# Qduino_Mini.net
KiCad netlist of a schematic drawn in EAGLE
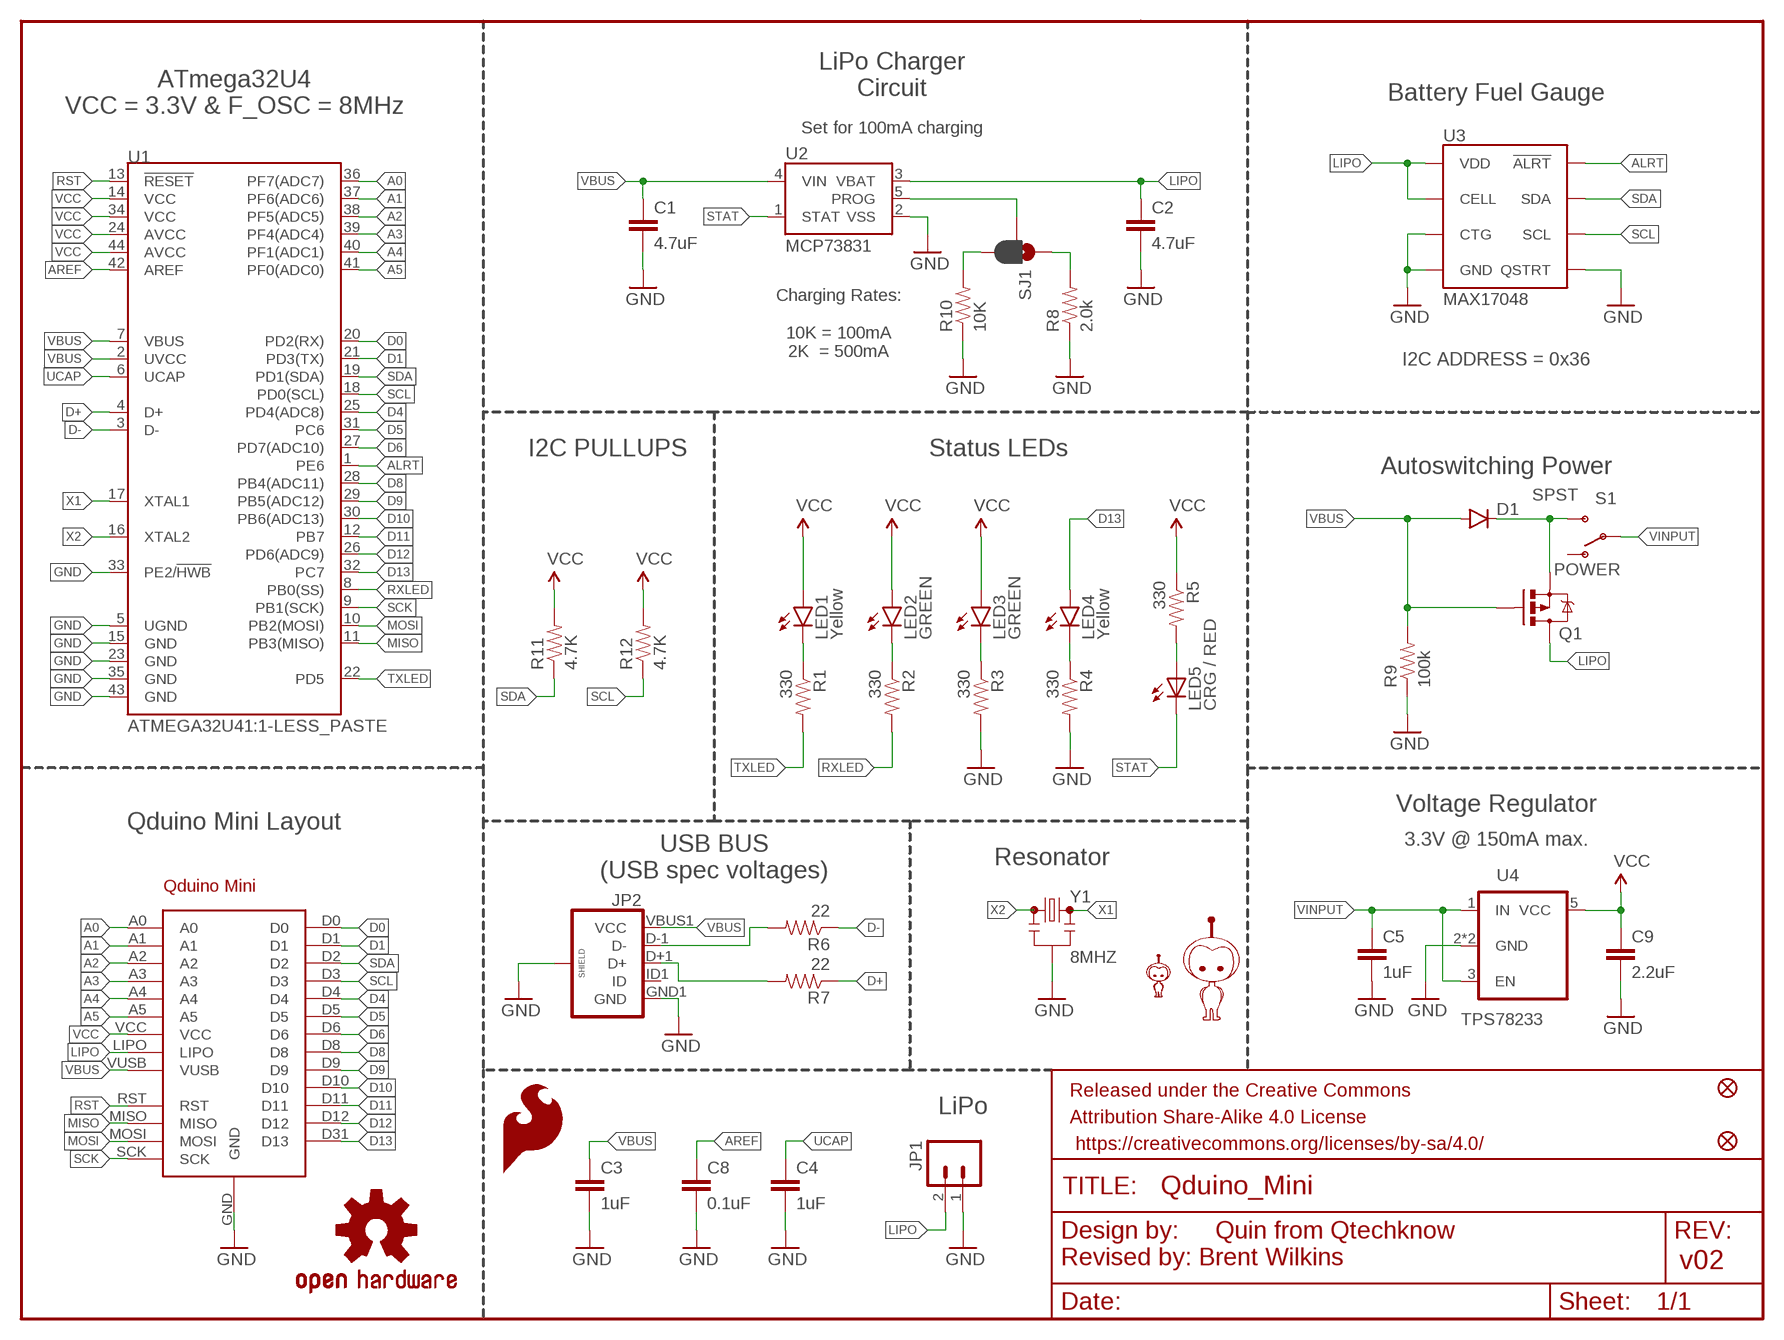
[diagram p0: schematic, sheet 1]

(export (version "E")
  (design (tool "Eeschema 10.0.6"))
  (components
    (comp (ref "C1")
      (value "4.7uF")
      (footprint "eagle-import:0603-CAP")
      (libsource (lib "eagle-import") (part "CAP0603-CAP"))
    )
    (comp (ref "C2")
      (value "4.7uF")
      (footprint "eagle-import:0603-CAP")
      (libsource (lib "eagle-import") (part "CAP0603-CAP"))
    )
    (comp (ref "C3")
      (value "1uF")
      (footprint "eagle-import:0603-CAP")
      (libsource (lib "eagle-import") (part "CAP0603-CAP"))
    )
    (comp (ref "C4")
      (value "1uF")
      (footprint "eagle-import:0603-CAP")
      (libsource (lib "eagle-import") (part "CAP0603-CAP"))
    )
    (comp (ref "C5")
      (value "1uF")
      (footprint "eagle-import:0603-CAP")
      (libsource (lib "eagle-import") (part "CAP0603-CAP"))
    )
    (comp (ref "C8")
      (value "0.1uF")
      (footprint "eagle-import:0603-CAP")
      (libsource (lib "eagle-import") (part "0.1UF-25V(+80/-20%)(0603)"))
    )
    (comp (ref "C9")
      (value "2.2uF")
      (footprint "eagle-import:0603-CAP")
      (libsource (lib "eagle-import") (part "2.2UF-10V-20%(0603)"))
    )
    (comp (ref "D1")
      (value "250mA/100V")
      (footprint "eagle-import:SOD-323")
      (libsource (lib "eagle-import") (part "DIODEBAS16"))
    )
    (comp (ref "FID5")
      (value "FIDUCIAL1X2")
      (footprint "eagle-import:FIDUCIAL-1X2")
      (libsource (lib "eagle-import") (part "FIDUCIAL1X2"))
    )
    (comp (ref "FID6")
      (value "FIDUCIAL1X2")
      (footprint "eagle-import:FIDUCIAL-1X2")
      (libsource (lib "eagle-import") (part "FIDUCIAL1X2"))
    )
    (comp (ref "FRAME2")
      (value "FRAME-LETTER")
      (footprint "eagle-import:CREATIVE_COMMONS")
      (fields (field (name "DESIGNER") "NAME"))
      (libsource (lib "eagle-import") (part "FRAME-LETTER"))
    )
    (comp (ref "JP1")
      (value "LiPo")
      (footprint "eagle-import:JST-2-SMD")
      (libsource (lib "eagle-import") (part "M02-JST-2MM-SMT"))
    )
    (comp (ref "JP2")
      (value "USB_MICROB_PLUGCONN-11752")
      (footprint "eagle-import:USB-B-MICRO-SMD_V03")
      (libsource (lib "eagle-import") (part "USB_MICROB_PLUGCONN-11752"))
    )
    (comp (ref "LED1")
      (value "Yellow")
      (footprint "eagle-import:LED-0603")
      (fields (field (name "PROD_ID") "DIO-09003"))
      (libsource (lib "eagle-import") (part "LED-YELLOW0603"))
    )
    (comp (ref "LED2")
      (value "GREEN")
      (footprint "eagle-import:LED-0603")
      (fields (field (name "PROD_ID") "DIO-00821"))
      (libsource (lib "eagle-import") (part "LED-GREEN0603"))
    )
    (comp (ref "LED3")
      (value "GREEN")
      (footprint "eagle-import:LED-0603")
      (fields (field (name "PROD_ID") "DIO-00821"))
      (libsource (lib "eagle-import") (part "LED-GREEN0603"))
    )
    (comp (ref "LED4")
      (value "Yellow")
      (footprint "eagle-import:LED-0603")
      (fields (field (name "PROD_ID") "DIO-09003"))
      (libsource (lib "eagle-import") (part "LED-YELLOW0603"))
    )
    (comp (ref "LED5")
      (value "CRG / RED")
      (footprint "eagle-import:LED-0603")
      (libsource (lib "eagle-import") (part "LED0603"))
    )
    (comp (ref "LOGO1")
      (value "OSHW-LOGOS")
      (footprint "eagle-import:OSHW-LOGO-S")
      (libsource (lib "eagle-import") (part "OSHW-LOGOS"))
    )
    (comp (ref "LOGO2")
      (value "SFE_LOGO_FLAME.1_INCH")
      (footprint "eagle-import:SFE_LOGO_FLAME_.1")
      (libsource (lib "eagle-import") (part "SFE_LOGO_FLAME.1_INCH"))
    )
    (comp (ref "Q1")
      (value "PFET")
      (footprint "eagle-import:SOT23-3")
      (libsource (lib "eagle-import") (part "MOSFET-PCHANNEL"))
    )
    (comp (ref "R1")
      (value "330")
      (footprint "eagle-import:0603-RES")
      (libsource (lib "eagle-import") (part "RESISTOR0603"))
    )
    (comp (ref "R2")
      (value "330")
      (footprint "eagle-import:0603-RES")
      (libsource (lib "eagle-import") (part "RESISTOR0603"))
    )
    (comp (ref "R3")
      (value "330")
      (footprint "eagle-import:0603-RES")
      (libsource (lib "eagle-import") (part "RESISTOR0603"))
    )
    (comp (ref "R4")
      (value "330")
      (footprint "eagle-import:0603-RES")
      (libsource (lib "eagle-import") (part "RESISTOR0603"))
    )
    (comp (ref "R5")
      (value "330")
      (footprint "eagle-import:0603-RES")
      (libsource (lib "eagle-import") (part "RESISTOR0603"))
    )
    (comp (ref "R6")
      (value "22")
      (footprint "eagle-import:0603-RES")
      (libsource (lib "eagle-import") (part "RESISTOR0603"))
    )
    (comp (ref "R7")
      (value "22")
      (footprint "eagle-import:0603-RES")
      (libsource (lib "eagle-import") (part "RESISTOR0603"))
    )
    (comp (ref "R8")
      (value "2.0k")
      (footprint "eagle-import:0603-RES")
      (libsource (lib "eagle-import") (part "2.0KOHM1/10W5%(0603)"))
    )
    (comp (ref "R9")
      (value "100k")
      (footprint "eagle-import:0603-RES")
      (libsource (lib "eagle-import") (part "100KOHM-1/10W-1%(0603)"))
    )
    (comp (ref "R10")
      (value "10K")
      (footprint "eagle-import:0603-RES")
      (libsource (lib "eagle-import") (part "10KOHM-1/10W-1%(0603)0603"))
    )
    (comp (ref "R11")
      (value "4.7K")
      (footprint "eagle-import:0603-RES")
      (libsource (lib "eagle-import") (part "RESISTOR0603-RES"))
    )
    (comp (ref "R12")
      (value "4.7K")
      (footprint "eagle-import:0603-RES")
      (libsource (lib "eagle-import") (part "RESISTOR0603-RES"))
    )
    (comp (ref "S1")
      (value "POWER")
      (footprint "eagle-import:SWITCH-SPST-SMD-A")
      (libsource (lib "eagle-import") (part "SWITCH-SPDT-SMD-A"))
    )
    (comp (ref "SJ1")
      (value "JUMPER-PAD-3-2OF3_NC_BY_PASTE")
      (footprint "eagle-import:PAD-JUMPER-3-2OF3_NC_BY_PASTE_YES_SILK_FULL_BOX")
      (libsource (lib "eagle-import") (part "JUMPER-PAD-3-2OF3_NC_BY_PASTE"))
    )
    (comp (ref "U1")
      (value "ATMEGA32U41:1-LESS_PASTE")
      (footprint "eagle-import:QFN-44-NOPAD_1_1-LESS_PASTE")
      (libsource (lib "eagle-import") (part "ATMEGA32U41{colon}1-LESS_PASTE"))
    )
    (comp (ref "U2")
      (value "MCP73831")
      (footprint "eagle-import:SOT23-5")
      (libsource (lib "eagle-import") (part "MCP73831"))
    )
    (comp (ref "U3")
      (value "MAX17048")
      (footprint "eagle-import:DFN-8")
      (libsource (lib "eagle-import") (part "MAX17048DFN8"))
    )
    (comp (ref "U4")
      (value "TPS78233")
      (footprint "eagle-import:SOT23-5")
      (libsource (lib "eagle-import") (part "LDO-TPS78233"))
    )
    (comp (ref "U5")
      (value "MIGHTYQ-L-SILK")
      (footprint "eagle-import:LOGO-LARGE-SILK")
      (libsource (lib "eagle-import") (part "MIGHTYQ-L-SILK"))
    )
    (comp (ref "U6")
      (value "MIGHTYQ-S-SILK")
      (footprint "eagle-import:LOGO-SMALL-SILK")
      (libsource (lib "eagle-import") (part "MIGHTYQ-S-SILK"))
    )
    (comp (ref "U7")
      (value "DNP")
      (footprint "eagle-import:QDUINO_MINI_V15")
      (libsource (lib "eagle-import") (part "QDUINOMINI"))
    )
    (comp (ref "Y1")
      (value "8MHZ")
      (footprint "eagle-import:RESONATOR-SMD")
      (libsource (lib "eagle-import") (part "RESONATOR8MHZ"))
    )
  )
  (nets
    (net (code "1") (name "A0") (class "Default")
      (node (ref "U1") (pin "36") (pinfunction "PF7(ADC7)_36") (pintype "bidirectional"))
      (node (ref "U7") (pin "A0") (pinfunction "A0_A0") (pintype "bidirectional"))
    )
    (net (code "2") (name "A1") (class "Default")
      (node (ref "U1") (pin "37") (pinfunction "PF6(ADC6)_37") (pintype "bidirectional"))
      (node (ref "U7") (pin "A1") (pinfunction "A1_A1") (pintype "bidirectional"))
    )
    (net (code "3") (name "A2") (class "Default")
      (node (ref "U1") (pin "38") (pinfunction "PF5(ADC5)_38") (pintype "bidirectional"))
      (node (ref "U7") (pin "A2") (pinfunction "A2_A2") (pintype "bidirectional"))
    )
    (net (code "4") (name "A3") (class "Default")
      (node (ref "U1") (pin "39") (pinfunction "PF4(ADC4)_39") (pintype "bidirectional"))
      (node (ref "U7") (pin "A3") (pinfunction "A3_A3") (pintype "bidirectional"))
    )
    (net (code "5") (name "A4") (class "Default")
      (node (ref "U1") (pin "40") (pinfunction "PF1(ADC1)_40") (pintype "bidirectional"))
      (node (ref "U7") (pin "A4") (pinfunction "A4_A4") (pintype "bidirectional"))
    )
    (net (code "6") (name "A5") (class "Default")
      (node (ref "U1") (pin "41") (pinfunction "PF0(ADC0)_41") (pintype "bidirectional"))
      (node (ref "U7") (pin "A5") (pinfunction "A5_A5") (pintype "bidirectional"))
    )
    (net (code "7") (name "ALRT") (class "Default")
      (node (ref "U1") (pin "1") (pinfunction "PE6_1") (pintype "bidirectional"))
      (node (ref "U3") (pin "P$5") (pinfunction "~{ALRT}_P$5") (pintype "bidirectional"))
    )
    (net (code "8") (name "AREF") (class "Default")
      (node (ref "C8") (pin "1") (pinfunction "1_1") (pintype "passive"))
      (node (ref "U1") (pin "42") (pinfunction "AREF_42") (pintype "bidirectional"))
    )
    (net (code "9") (name "D+") (class "Default")
      (node (ref "R7") (pin "1") (pinfunction "1_1") (pintype "passive"))
      (node (ref "U1") (pin "4") (pinfunction "D+_4") (pintype "bidirectional"))
    )
    (net (code "10") (name "D-") (class "Default")
      (node (ref "R6") (pin "1") (pinfunction "1_1") (pintype "passive"))
      (node (ref "U1") (pin "3") (pinfunction "D-_3") (pintype "bidirectional"))
    )
    (net (code "11") (name "D0") (class "Default")
      (node (ref "U1") (pin "20") (pinfunction "PD2(RX)_20") (pintype "bidirectional"))
      (node (ref "U7") (pin "D0") (pinfunction "D0_D0") (pintype "bidirectional"))
    )
    (net (code "12") (name "D1") (class "Default")
      (node (ref "U1") (pin "21") (pinfunction "PD3(TX)_21") (pintype "bidirectional"))
      (node (ref "U7") (pin "D1") (pinfunction "D1_D1") (pintype "bidirectional"))
    )
    (net (code "13") (name "D4") (class "Default")
      (node (ref "U1") (pin "25") (pinfunction "PD4(ADC8)_25") (pintype "bidirectional"))
      (node (ref "U7") (pin "D4") (pinfunction "D4_D4") (pintype "bidirectional"))
    )
    (net (code "14") (name "D5") (class "Default")
      (node (ref "U1") (pin "31") (pinfunction "PC6_31") (pintype "bidirectional"))
      (node (ref "U7") (pin "D5") (pinfunction "D5_D5") (pintype "bidirectional"))
    )
    (net (code "15") (name "D6") (class "Default")
      (node (ref "U1") (pin "27") (pinfunction "PD7(ADC10)_27") (pintype "bidirectional"))
      (node (ref "U7") (pin "D6") (pinfunction "D6_D6") (pintype "bidirectional"))
    )
    (net (code "16") (name "D8") (class "Default")
      (node (ref "U1") (pin "28") (pinfunction "PB4(ADC11)_28") (pintype "bidirectional"))
      (node (ref "U7") (pin "D8") (pinfunction "D8_D8") (pintype "bidirectional"))
    )
    (net (code "17") (name "D9") (class "Default")
      (node (ref "U1") (pin "29") (pinfunction "PB5(ADC12)_29") (pintype "bidirectional"))
      (node (ref "U7") (pin "D9") (pinfunction "D9_D9") (pintype "bidirectional"))
    )
    (net (code "18") (name "D10") (class "Default")
      (node (ref "U1") (pin "30") (pinfunction "PB6(ADC13)_30") (pintype "bidirectional"))
      (node (ref "U7") (pin "D10") (pinfunction "D10_D10") (pintype "bidirectional"))
    )
    (net (code "19") (name "D11") (class "Default")
      (node (ref "U1") (pin "12") (pinfunction "PB7_12") (pintype "bidirectional"))
      (node (ref "U7") (pin "D11") (pinfunction "D11_D11") (pintype "bidirectional"))
    )
    (net (code "20") (name "D12") (class "Default")
      (node (ref "U1") (pin "26") (pinfunction "PD6(ADC9)_26") (pintype "bidirectional"))
      (node (ref "U7") (pin "D12") (pinfunction "D12_D12") (pintype "bidirectional"))
    )
    (net (code "21") (name "D13") (class "Default")
      (node (ref "LED4") (pin "A") (pinfunction "A_A") (pintype "passive"))
      (node (ref "U1") (pin "32") (pinfunction "PC7_32") (pintype "bidirectional"))
      (node (ref "U7") (pin "D31") (pinfunction "D13_D31") (pintype "bidirectional"))
    )
    (net (code "22") (name "GND") (class "Default")
      (node (ref "C1") (pin "2") (pinfunction "2_2") (pintype "passive"))
      (node (ref "C2") (pin "2") (pinfunction "2_2") (pintype "passive"))
      (node (ref "C3") (pin "2") (pinfunction "2_2") (pintype "passive"))
      (node (ref "C4") (pin "2") (pinfunction "2_2") (pintype "passive"))
      (node (ref "C5") (pin "2") (pinfunction "2_2") (pintype "passive"))
      (node (ref "C8") (pin "2") (pinfunction "2_2") (pintype "passive"))
      (node (ref "C9") (pin "2") (pinfunction "2_2") (pintype "passive"))
      (node (ref "JP1") (pin "1") (pinfunction "1_1") (pintype "passive"))
      (node (ref "JP2") (pin "GND1") (pinfunction "GND_GND1") (pintype "bidirectional"))
      (node (ref "JP2") (pin "SHIELD1") (pinfunction "SHIELD_SHIELD1") (pintype "bidirectional"))
      (node (ref "JP2") (pin "SHIELD2") (pinfunction "SHIELD_SHIELD2") (pintype "bidirectional"))
      (node (ref "JP2") (pin "SHIELD3") (pinfunction "SHIELD_SHIELD3") (pintype "bidirectional"))
      (node (ref "R10") (pin "1") (pinfunction "1_1") (pintype "passive"))
      (node (ref "R3") (pin "2") (pinfunction "2_2") (pintype "passive"))
      (node (ref "R4") (pin "2") (pinfunction "2_2") (pintype "passive"))
      (node (ref "R8") (pin "1") (pinfunction "1_1") (pintype "passive"))
      (node (ref "R9") (pin "1") (pinfunction "1_1") (pintype "passive"))
      (node (ref "U1") (pin "15") (pinfunction "GND_15") (pintype "bidirectional"))
      (node (ref "U1") (pin "23") (pinfunction "GND_23") (pintype "bidirectional"))
      (node (ref "U1") (pin "33") (pinfunction "PE2/~{HWB}_33") (pintype "bidirectional"))
      (node (ref "U1") (pin "35") (pinfunction "GND_35") (pintype "bidirectional"))
      (node (ref "U1") (pin "43") (pinfunction "GND_43") (pintype "bidirectional"))
      (node (ref "U1") (pin "5") (pinfunction "UGND_5") (pintype "bidirectional"))
      (node (ref "U2") (pin "2") (pinfunction "VSS_2") (pintype "power_in"))
      (node (ref "U3") (pin "P$1") (pinfunction "CTG_P$1") (pintype "input"))
      (node (ref "U3") (pin "P$4") (pinfunction "GND_P$4") (pintype "bidirectional"))
      (node (ref "U3") (pin "P$6") (pinfunction "QSTRT_P$6") (pintype "bidirectional"))
      (node (ref "U3") (pin "P$9") (pinfunction "GND_P$9") (pintype "bidirectional"))
      (node (ref "U4") (pin "2") (pinfunction "GND_2") (pintype "input"))
      (node (ref "U4") (pin "4") (pinfunction "GND_4") (pintype "input"))
      (node (ref "U7") (pin "GND") (pinfunction "GND_GND") (pintype "bidirectional"))
      (node (ref "Y1") (pin "2") (pinfunction "2_2") (pintype "passive"))
    )
    (net (code "23") (name "LIPO") (class "Default")
      (node (ref "C2") (pin "1") (pinfunction "1_1") (pintype "passive"))
      (node (ref "JP1") (pin "2") (pinfunction "2_2") (pintype "passive"))
      (node (ref "Q1") (pin "3") (pinfunction "D_3") (pintype "passive"))
      (node (ref "U2") (pin "3") (pinfunction "VBAT_3") (pintype "power_in"))
      (node (ref "U3") (pin "P$2") (pinfunction "CELL_P$2") (pintype "input"))
      (node (ref "U3") (pin "P$3") (pinfunction "VDD_P$3") (pintype "bidirectional"))
      (node (ref "U7") (pin "LIPO") (pinfunction "LIPO_LIPO") (pintype "bidirectional"))
    )
    (net (code "24") (name "MISO") (class "Default")
      (node (ref "U1") (pin "11") (pinfunction "PB3(MISO)_11") (pintype "bidirectional"))
      (node (ref "U7") (pin "MISO") (pinfunction "MISO_MISO") (pintype "bidirectional"))
    )
    (net (code "25") (name "MOSI") (class "Default")
      (node (ref "U1") (pin "10") (pinfunction "PB2(MOSI)_10") (pintype "bidirectional"))
      (node (ref "U7") (pin "MOSI") (pinfunction "MOSI_MOSI") (pintype "bidirectional"))
    )
    (net (code "26") (name "Net-(JP2-D+)") (class "Default")
      (node (ref "JP2") (pin "D+1") (pinfunction "D+_D+1") (pintype "bidirectional"))
      (node (ref "R7") (pin "2") (pinfunction "2_2") (pintype "passive"))
    )
    (net (code "27") (name "Net-(JP2-D-)") (class "Default")
      (node (ref "JP2") (pin "D-1") (pinfunction "D-_D-1") (pintype "bidirectional"))
      (node (ref "R6") (pin "2") (pinfunction "2_2") (pintype "passive"))
    )
    (net (code "28") (name "Net-(LED1-PadC)") (class "Default")
      (node (ref "LED1") (pin "C") (pinfunction "C_C") (pintype "passive"))
      (node (ref "R1") (pin "1") (pinfunction "1_1") (pintype "passive"))
    )
    (net (code "29") (name "Net-(LED2-PadC)") (class "Default")
      (node (ref "LED2") (pin "C") (pinfunction "C_C") (pintype "passive"))
      (node (ref "R2") (pin "1") (pinfunction "1_1") (pintype "passive"))
    )
    (net (code "30") (name "Net-(LED3-PadC)") (class "Default")
      (node (ref "LED3") (pin "C") (pinfunction "C_C") (pintype "passive"))
      (node (ref "R3") (pin "1") (pinfunction "1_1") (pintype "passive"))
    )
    (net (code "31") (name "Net-(LED4-PadC)") (class "Default")
      (node (ref "LED4") (pin "C") (pinfunction "C_C") (pintype "passive"))
      (node (ref "R4") (pin "1") (pinfunction "1_1") (pintype "passive"))
    )
    (net (code "32") (name "Net-(LED5-PadA)") (class "Default")
      (node (ref "LED5") (pin "A") (pinfunction "A_A") (pintype "passive"))
      (node (ref "R5") (pin "2") (pinfunction "2_2") (pintype "passive"))
    )
    (net (code "33") (name "Net-(Q1-S)") (class "Default")
      (node (ref "D1") (pin "C") (pinfunction "C_C") (pintype "passive"))
      (node (ref "Q1") (pin "2") (pinfunction "S_2") (pintype "passive"))
      (node (ref "S1") (pin "3") (pinfunction "S_3") (pintype "passive"))
    )
    (net (code "34") (name "Net-(R8-Pad2)") (class "Default")
      (node (ref "R8") (pin "2") (pinfunction "2_2") (pintype "passive"))
      (node (ref "SJ1") (pin "1") (pinfunction "1_1") (pintype "passive"))
    )
    (net (code "35") (name "Net-(R10-Pad2)") (class "Default")
      (node (ref "R10") (pin "2") (pinfunction "2_2") (pintype "passive"))
      (node (ref "SJ1") (pin "3") (pinfunction "3_3") (pintype "passive"))
    )
    (net (code "36") (name "Net-(U2-PROG)") (class "Default")
      (node (ref "SJ1") (pin "2") (pinfunction "2_2") (pintype "passive"))
      (node (ref "U2") (pin "5") (pinfunction "PROG_5") (pintype "input"))
    )
    (net (code "37") (name "RST") (class "Default")
      (node (ref "U1") (pin "13") (pinfunction "~{RESET}_13") (pintype "bidirectional"))
      (node (ref "U7") (pin "RST") (pinfunction "RST_RST") (pintype "bidirectional"))
    )
    (net (code "38") (name "RXLED") (class "Default")
      (node (ref "R2") (pin "2") (pinfunction "2_2") (pintype "passive"))
      (node (ref "U1") (pin "8") (pinfunction "PB0(SS)_8") (pintype "bidirectional"))
    )
    (net (code "39") (name "SCK") (class "Default")
      (node (ref "U1") (pin "9") (pinfunction "PB1(SCK)_9") (pintype "bidirectional"))
      (node (ref "U7") (pin "SCK") (pinfunction "SCK_SCK") (pintype "bidirectional"))
    )
    (net (code "40") (name "SCL") (class "Default")
      (node (ref "R12") (pin "1") (pinfunction "1_1") (pintype "passive"))
      (node (ref "U1") (pin "18") (pinfunction "PD0(SCL)_18") (pintype "bidirectional"))
      (node (ref "U3") (pin "P$7") (pinfunction "SCL_P$7") (pintype "output"))
      (node (ref "U7") (pin "D3") (pinfunction "D3_D3") (pintype "bidirectional"))
    )
    (net (code "41") (name "SDA") (class "Default")
      (node (ref "R11") (pin "1") (pinfunction "1_1") (pintype "passive"))
      (node (ref "U1") (pin "19") (pinfunction "PD1(SDA)_19") (pintype "bidirectional"))
      (node (ref "U3") (pin "P$8") (pinfunction "SDA_P$8") (pintype "input"))
      (node (ref "U7") (pin "D2") (pinfunction "D2_D2") (pintype "bidirectional"))
    )
    (net (code "42") (name "STAT") (class "Default")
      (node (ref "LED5") (pin "C") (pinfunction "C_C") (pintype "passive"))
      (node (ref "U2") (pin "1") (pinfunction "STAT_1") (pintype "output"))
    )
    (net (code "43") (name "TXLED") (class "Default")
      (node (ref "R1") (pin "2") (pinfunction "2_2") (pintype "passive"))
      (node (ref "U1") (pin "22") (pinfunction "PD5_22") (pintype "bidirectional"))
    )
    (net (code "44") (name "UCAP") (class "Default")
      (node (ref "C4") (pin "1") (pinfunction "1_1") (pintype "passive"))
      (node (ref "U1") (pin "6") (pinfunction "UCAP_6") (pintype "bidirectional"))
    )
    (net (code "45") (name "VBUS") (class "Default")
      (node (ref "C1") (pin "1") (pinfunction "1_1") (pintype "passive"))
      (node (ref "C3") (pin "1") (pinfunction "1_1") (pintype "passive"))
      (node (ref "D1") (pin "A") (pinfunction "A_A") (pintype "passive"))
      (node (ref "JP2") (pin "VBUS1") (pinfunction "VCC_VBUS1") (pintype "bidirectional"))
      (node (ref "Q1") (pin "1") (pinfunction "G_1") (pintype "passive"))
      (node (ref "R9") (pin "2") (pinfunction "2_2") (pintype "passive"))
      (node (ref "U1") (pin "2") (pinfunction "UVCC_2") (pintype "bidirectional"))
      (node (ref "U1") (pin "7") (pinfunction "VBUS_7") (pintype "bidirectional"))
      (node (ref "U2") (pin "4") (pinfunction "VIN_4") (pintype "power_in"))
      (node (ref "U7") (pin "VUSB") (pinfunction "VUSB_VUSB") (pintype "bidirectional"))
    )
    (net (code "46") (name "VCC") (class "Default")
      (node (ref "C9") (pin "1") (pinfunction "1_1") (pintype "passive"))
      (node (ref "LED1") (pin "A") (pinfunction "A_A") (pintype "passive"))
      (node (ref "LED2") (pin "A") (pinfunction "A_A") (pintype "passive"))
      (node (ref "LED3") (pin "A") (pinfunction "A_A") (pintype "passive"))
      (node (ref "R11") (pin "2") (pinfunction "2_2") (pintype "passive"))
      (node (ref "R12") (pin "2") (pinfunction "2_2") (pintype "passive"))
      (node (ref "R5") (pin "1") (pinfunction "1_1") (pintype "passive"))
      (node (ref "U1") (pin "14") (pinfunction "VCC_14") (pintype "bidirectional"))
      (node (ref "U1") (pin "24") (pinfunction "AVCC_24") (pintype "bidirectional"))
      (node (ref "U1") (pin "34") (pinfunction "VCC_34") (pintype "bidirectional"))
      (node (ref "U1") (pin "44") (pinfunction "AVCC_44") (pintype "bidirectional"))
      (node (ref "U4") (pin "5") (pinfunction "VCC_5") (pintype "power_in"))
      (node (ref "U7") (pin "VCC") (pinfunction "VCC_VCC") (pintype "bidirectional"))
    )
    (net (code "47") (name "VINPUT") (class "Default")
      (node (ref "C5") (pin "1") (pinfunction "1_1") (pintype "passive"))
      (node (ref "S1") (pin "2") (pinfunction "P_2") (pintype "passive"))
      (node (ref "U4") (pin "1") (pinfunction "IN_1") (pintype "input"))
      (node (ref "U4") (pin "3") (pinfunction "EN_3") (pintype "input"))
    )
    (net (code "48") (name "X1") (class "Default")
      (node (ref "U1") (pin "17") (pinfunction "XTAL1_17") (pintype "bidirectional"))
      (node (ref "Y1") (pin "3") (pinfunction "3_3") (pintype "passive"))
    )
    (net (code "49") (name "X2") (class "Default")
      (node (ref "U1") (pin "16") (pinfunction "XTAL2_16") (pintype "bidirectional"))
      (node (ref "Y1") (pin "1") (pinfunction "1_1") (pintype "passive"))
    )
    (net (code "50") (name "unconnected-(JP2-ID-PadID1)") (class "Default")
      (node (ref "JP2") (pin "ID1") (pinfunction "ID_ID1") (pintype "bidirectional"))
    )
    (net (code "51") (name "unconnected-(S1-O-Pad1)") (class "Default")
      (node (ref "S1") (pin "1") (pinfunction "O_1") (pintype "passive"))
    )
  )
)
